# WorkerB.net
KiCad netlist of a schematic drawn in EAGLE
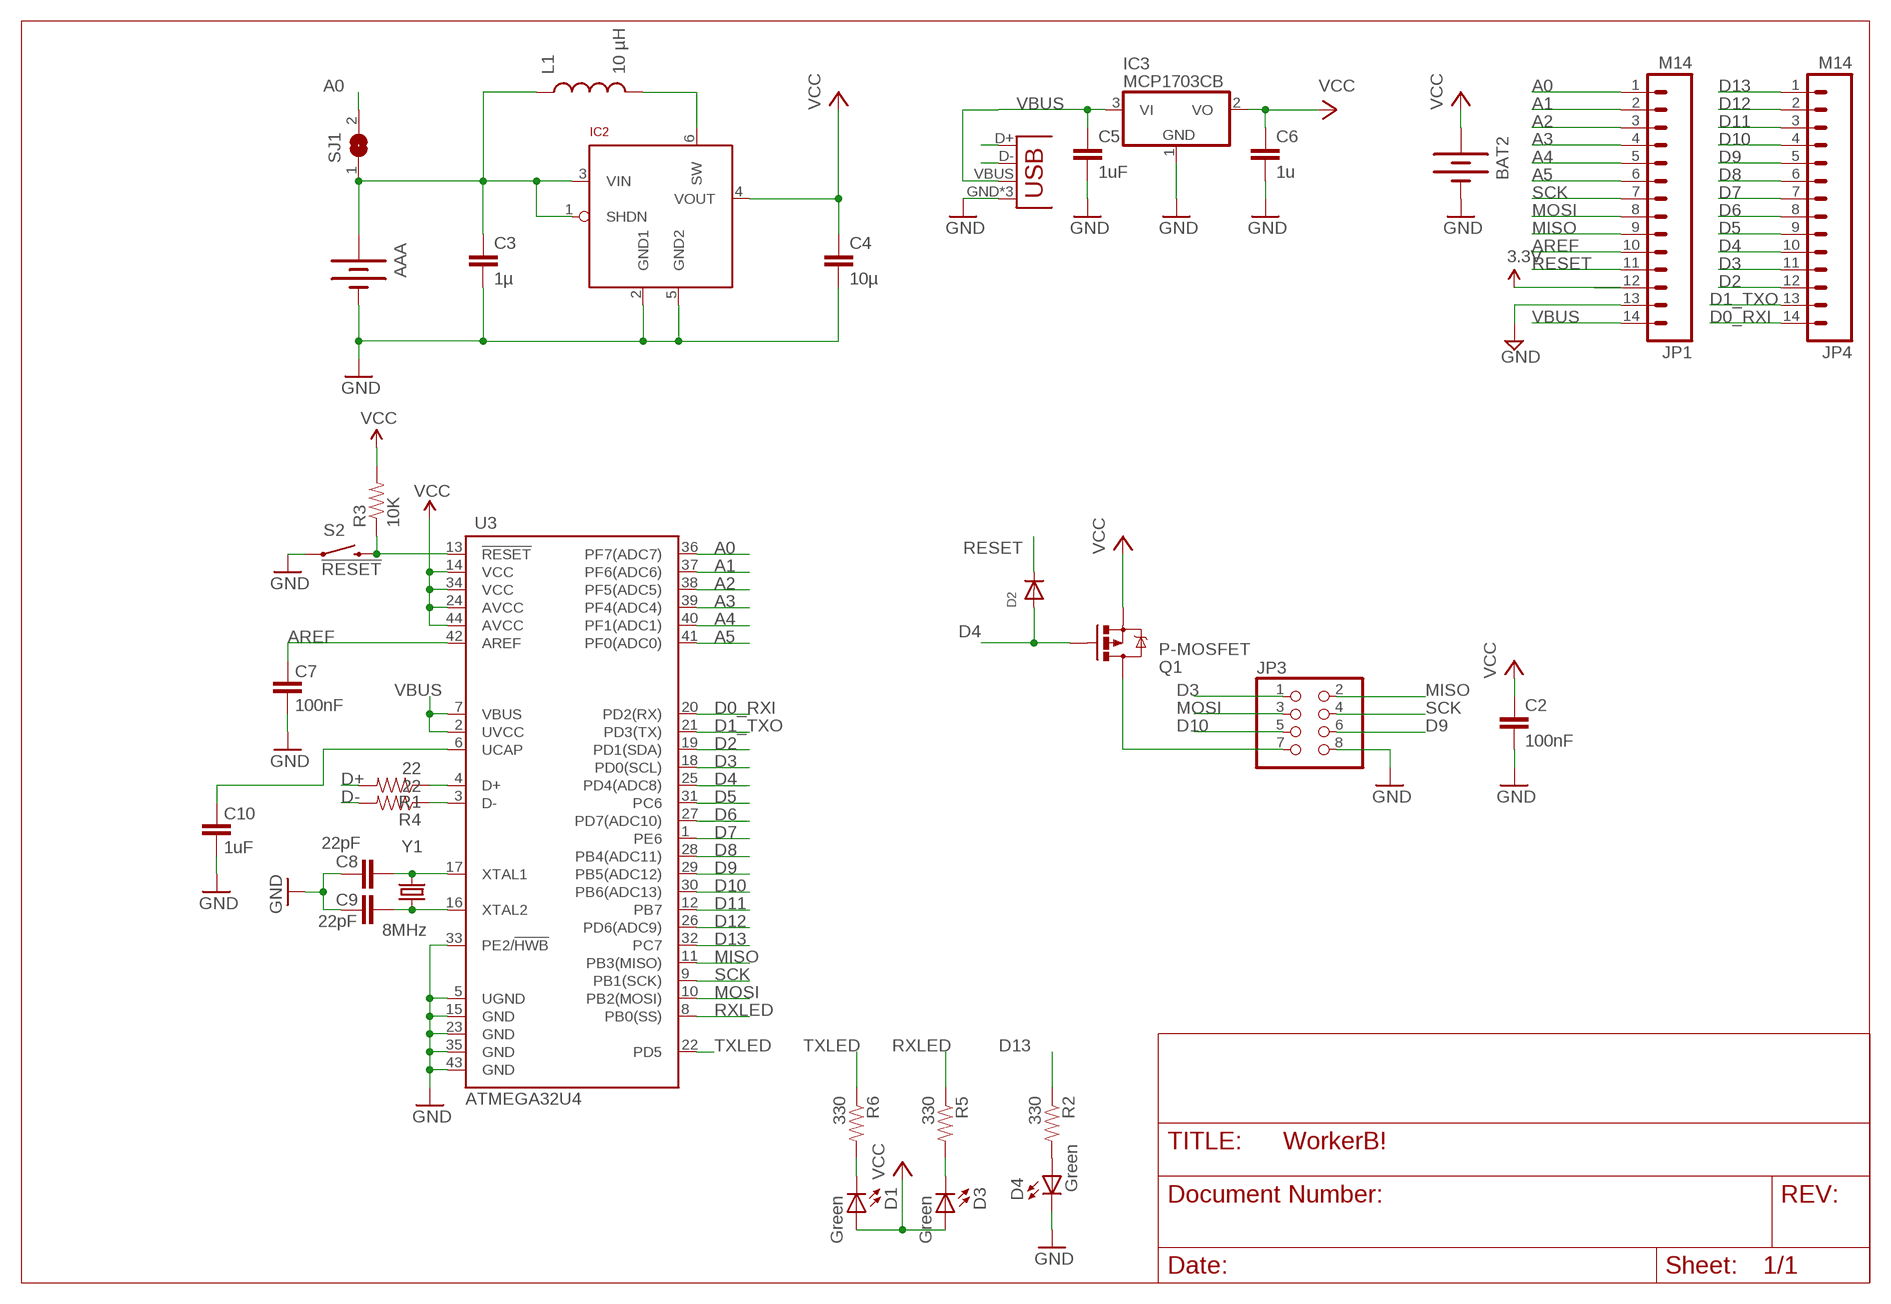
[diagram p0: schematic, sheet 1]

(export (version "E")
  (design (tool "Eeschema 10.0.6"))
  (components
    (comp (ref "AAA")
      (value "BATTERYAAA-JL")
      (footprint "eagle-import:BATTERY-AAA-JL")
      (libsource (lib "eagle-import") (part "BATTERYAAA-JL"))
    )
    (comp (ref "BAT2")
      (value "BATTERY20PTH")
      (footprint "eagle-import:BATTCOM_20MM_PTH")
      (libsource (lib "eagle-import") (part "SparkFun_BATTERY20PTH"))
    )
    (comp (ref "C2")
      (value "100nF")
      (footprint "eagle-import:C0603K")
      (libsource (lib "eagle-import") (part "C-EUC0603K"))
    )
    (comp (ref "C3")
      (value "1µ")
      (footprint "eagle-import:0603-CAP")
      (libsource (lib "eagle-import") (part "CAP0603-CAP"))
    )
    (comp (ref "C4")
      (value "10µ")
      (footprint "eagle-import:0805")
      (libsource (lib "eagle-import") (part "CAP0805"))
    )
    (comp (ref "C5")
      (value "1uF")
      (footprint "eagle-import:C0603K")
      (libsource (lib "eagle-import") (part "C-EUC0603K"))
    )
    (comp (ref "C6")
      (value "1u")
      (footprint "eagle-import:C0603K")
      (libsource (lib "eagle-import") (part "C-EUC0603K"))
    )
    (comp (ref "C7")
      (value "100nF")
      (footprint "eagle-import:0402-CAP")
      (libsource (lib "eagle-import") (part "CAP0402-CAP"))
    )
    (comp (ref "C8")
      (value "22pF")
      (footprint "eagle-import:0402-CAP")
      (libsource (lib "eagle-import") (part "CAP0402-CAP"))
    )
    (comp (ref "C9")
      (value "22pF")
      (footprint "eagle-import:0402-CAP")
      (libsource (lib "eagle-import") (part "CAP0402-CAP"))
    )
    (comp (ref "C10")
      (value "1uF")
      (footprint "eagle-import:0402-CAP")
      (libsource (lib "eagle-import") (part "CAP0402-CAP"))
    )
    (comp (ref "D1")
      (value "Green")
      (footprint "eagle-import:LED-0603")
      (libsource (lib "eagle-import") (part "LED0603"))
    )
    (comp (ref "D2")
      (value "DIODESOD-323F")
      (footprint "eagle-import:SOD-323F")
      (libsource (lib "eagle-import") (part "DIODESOD-323F"))
    )
    (comp (ref "D3")
      (value "Green")
      (footprint "eagle-import:LED-0603")
      (libsource (lib "eagle-import") (part "LED0603"))
    )
    (comp (ref "D4")
      (value "Green")
      (footprint "eagle-import:LED-0603")
      (libsource (lib "eagle-import") (part "LED0603"))
    )
    (comp (ref "IC2")
      (value "LTC3525")
      (footprint "eagle-import:SC70")
      (libsource (lib "eagle-import") (part "LTC3525"))
    )
    (comp (ref "IC3")
      (value "MCP1703CB")
      (footprint "eagle-import:SOT23")
      (libsource (lib "eagle-import") (part "MCP1703CB"))
    )
    (comp (ref "JP1")
      (value "M14")
      (footprint "eagle-import:1X14")
      (libsource (lib "eagle-import") (part "M14"))
    )
    (comp (ref "JP2")
      (value "USB-MICROB")
      (footprint "eagle-import:USB-MICROB")
      (libsource (lib "eagle-import") (part "USB-MICROB"))
    )
    (comp (ref "JP3")
      (value "PINHD-2X4")
      (footprint "eagle-import:2X04")
      (libsource (lib "eagle-import") (part "PINHD-2X4"))
    )
    (comp (ref "JP4")
      (value "M14")
      (footprint "eagle-import:1X14")
      (libsource (lib "eagle-import") (part "M14"))
    )
    (comp (ref "L1")
      (value "10 µH")
      (footprint "eagle-import:1210")
      (libsource (lib "eagle-import") (part "INDUCTOR1210"))
    )
    (comp (ref "Q1")
      (value "P-MOSFET")
      (footprint "eagle-import:SOT23")
      (libsource (lib "eagle-import") (part "MOSFET-PCHANNEL"))
    )
    (comp (ref "R1")
      (value "22")
      (footprint "eagle-import:0402-RES")
      (libsource (lib "eagle-import") (part "RESISTOR0402-RES"))
    )
    (comp (ref "R2")
      (value "330")
      (footprint "eagle-import:0402-RES")
      (libsource (lib "eagle-import") (part "RESISTOR0402-RES"))
    )
    (comp (ref "R3")
      (value "10K")
      (footprint "eagle-import:0402-RES")
      (libsource (lib "eagle-import") (part "RESISTOR0402-RES"))
    )
    (comp (ref "R4")
      (value "22")
      (footprint "eagle-import:0402-RES")
      (libsource (lib "eagle-import") (part "RESISTOR0402-RES"))
    )
    (comp (ref "R5")
      (value "330")
      (footprint "eagle-import:0402-RES")
      (libsource (lib "eagle-import") (part "RESISTOR0402-RES"))
    )
    (comp (ref "R6")
      (value "330")
      (footprint "eagle-import:0402-RES")
      (libsource (lib "eagle-import") (part "RESISTOR0402-RES"))
    )
    (comp (ref "S2")
      (value "!RESET")
      (footprint "eagle-import:TACTILE_SWITCH_SMD")
      (libsource (lib "eagle-import") (part "SWITCH-MOMENTARY-2SMD"))
    )
    (comp (ref "SJ1") (value "SJ") (footprint "eagle-import:SJ") (libsource (lib "eagle-import") (part "SJ")))
    (comp (ref "U3")
      (value "ATMEGA32U4")
      (footprint "eagle-import:QFN-44-NOPAD")
      (libsource (lib "eagle-import") (part "ATMEGA32U4QFN2"))
    )
    (comp (ref "Y1")
      (value "8MHz")
      (footprint "eagle-import:CRYSTAL-SMD-5X3")
      (libsource (lib "eagle-import") (part "CRYSTAL5X3"))
    )
  )
  (nets
    (net (code "1") (name "/A0") (class "Default")
      (node (ref "JP1") (pin "1") (pinfunction "1_1") (pintype "passive"))
      (node (ref "SJ1") (pin "2") (pinfunction "2_2") (pintype "passive"))
      (node (ref "U3") (pin "36") (pinfunction "PF7(ADC7)_36") (pintype "bidirectional"))
    )
    (net (code "2") (name "/A1") (class "Default")
      (node (ref "JP1") (pin "2") (pinfunction "2_2") (pintype "passive"))
      (node (ref "U3") (pin "37") (pinfunction "PF6(ADC6)_37") (pintype "bidirectional"))
    )
    (net (code "3") (name "/A2") (class "Default")
      (node (ref "JP1") (pin "3") (pinfunction "3_3") (pintype "passive"))
      (node (ref "U3") (pin "38") (pinfunction "PF5(ADC5)_38") (pintype "bidirectional"))
    )
    (net (code "4") (name "/A3") (class "Default")
      (node (ref "JP1") (pin "4") (pinfunction "4_4") (pintype "passive"))
      (node (ref "U3") (pin "39") (pinfunction "PF4(ADC4)_39") (pintype "bidirectional"))
    )
    (net (code "5") (name "/A4") (class "Default")
      (node (ref "JP1") (pin "5") (pinfunction "5_5") (pintype "passive"))
      (node (ref "U3") (pin "40") (pinfunction "PF1(ADC1)_40") (pintype "bidirectional"))
    )
    (net (code "6") (name "/A5") (class "Default")
      (node (ref "JP1") (pin "6") (pinfunction "6_6") (pintype "passive"))
      (node (ref "U3") (pin "41") (pinfunction "PF0(ADC0)_41") (pintype "bidirectional"))
    )
    (net (code "7") (name "/AREF") (class "Default")
      (node (ref "C7") (pin "2") (pinfunction "2_2") (pintype "passive"))
      (node (ref "JP1") (pin "10") (pinfunction "10_10") (pintype "passive"))
      (node (ref "U3") (pin "42") (pinfunction "AREF_42") (pintype "bidirectional"))
    )
    (net (code "8") (name "/D+") (class "Default")
      (node (ref "JP2") (pin "D+") (pinfunction "D+_D+") (pintype "bidirectional"))
      (node (ref "R1") (pin "2") (pinfunction "2_2") (pintype "passive"))
    )
    (net (code "9") (name "/D-") (class "Default")
      (node (ref "JP2") (pin "D-") (pinfunction "D-_D-") (pintype "bidirectional"))
      (node (ref "R4") (pin "2") (pinfunction "2_2") (pintype "passive"))
    )
    (net (code "10") (name "/D0_RXI") (class "Default")
      (node (ref "JP4") (pin "14") (pinfunction "14_14") (pintype "passive"))
      (node (ref "U3") (pin "20") (pinfunction "PD2(RX)_20") (pintype "bidirectional"))
    )
    (net (code "11") (name "/D1_TXO") (class "Default")
      (node (ref "JP4") (pin "13") (pinfunction "13_13") (pintype "passive"))
      (node (ref "U3") (pin "21") (pinfunction "PD3(TX)_21") (pintype "bidirectional"))
    )
    (net (code "12") (name "/D2") (class "Default")
      (node (ref "JP4") (pin "12") (pinfunction "12_12") (pintype "passive"))
      (node (ref "U3") (pin "19") (pinfunction "PD1(SDA)_19") (pintype "bidirectional"))
    )
    (net (code "13") (name "/D3") (class "Default")
      (node (ref "JP3") (pin "1") (pinfunction "1_1") (pintype "passive"))
      (node (ref "JP4") (pin "11") (pinfunction "11_11") (pintype "passive"))
      (node (ref "U3") (pin "18") (pinfunction "PD0(SCL)_18") (pintype "bidirectional"))
    )
    (net (code "14") (name "/D4") (class "Default")
      (node (ref "D2") (pin "A") (pinfunction "A_A") (pintype "passive"))
      (node (ref "JP4") (pin "10") (pinfunction "10_10") (pintype "passive"))
      (node (ref "Q1") (pin "1") (pinfunction "G_1") (pintype "passive"))
      (node (ref "U3") (pin "25") (pinfunction "PD4(ADC8)_25") (pintype "bidirectional"))
    )
    (net (code "15") (name "/D5") (class "Default")
      (node (ref "JP4") (pin "9") (pinfunction "9_9") (pintype "passive"))
      (node (ref "U3") (pin "31") (pinfunction "PC6_31") (pintype "bidirectional"))
    )
    (net (code "16") (name "/D6") (class "Default")
      (node (ref "JP4") (pin "8") (pinfunction "8_8") (pintype "passive"))
      (node (ref "U3") (pin "27") (pinfunction "PD7(ADC10)_27") (pintype "bidirectional"))
    )
    (net (code "17") (name "/D7") (class "Default")
      (node (ref "JP4") (pin "7") (pinfunction "7_7") (pintype "passive"))
      (node (ref "U3") (pin "1") (pinfunction "PE6_1") (pintype "bidirectional"))
    )
    (net (code "18") (name "/D8") (class "Default")
      (node (ref "JP4") (pin "6") (pinfunction "6_6") (pintype "passive"))
      (node (ref "U3") (pin "28") (pinfunction "PB4(ADC11)_28") (pintype "bidirectional"))
    )
    (net (code "19") (name "/D9") (class "Default")
      (node (ref "JP3") (pin "6") (pinfunction "6_6") (pintype "passive"))
      (node (ref "JP4") (pin "5") (pinfunction "5_5") (pintype "passive"))
      (node (ref "U3") (pin "29") (pinfunction "PB5(ADC12)_29") (pintype "bidirectional"))
    )
    (net (code "20") (name "/D10") (class "Default")
      (node (ref "JP3") (pin "5") (pinfunction "5_5") (pintype "passive"))
      (node (ref "JP4") (pin "4") (pinfunction "4_4") (pintype "passive"))
      (node (ref "U3") (pin "30") (pinfunction "PB6(ADC13)_30") (pintype "bidirectional"))
    )
    (net (code "21") (name "/D11") (class "Default")
      (node (ref "JP4") (pin "3") (pinfunction "3_3") (pintype "passive"))
      (node (ref "U3") (pin "12") (pinfunction "PB7_12") (pintype "bidirectional"))
    )
    (net (code "22") (name "/D12") (class "Default")
      (node (ref "JP4") (pin "2") (pinfunction "2_2") (pintype "passive"))
      (node (ref "U3") (pin "26") (pinfunction "PD6(ADC9)_26") (pintype "bidirectional"))
    )
    (net (code "23") (name "/D13") (class "Default")
      (node (ref "JP4") (pin "1") (pinfunction "1_1") (pintype "passive"))
      (node (ref "R2") (pin "1") (pinfunction "1_1") (pintype "passive"))
      (node (ref "U3") (pin "32") (pinfunction "PC7_32") (pintype "bidirectional"))
    )
    (net (code "24") (name "/MISO") (class "Default")
      (node (ref "JP1") (pin "9") (pinfunction "9_9") (pintype "passive"))
      (node (ref "JP3") (pin "2") (pinfunction "2_2") (pintype "passive"))
      (node (ref "U3") (pin "11") (pinfunction "PB3(MISO)_11") (pintype "bidirectional"))
    )
    (net (code "25") (name "/MOSI") (class "Default")
      (node (ref "JP1") (pin "8") (pinfunction "8_8") (pintype "passive"))
      (node (ref "JP3") (pin "3") (pinfunction "3_3") (pintype "passive"))
      (node (ref "U3") (pin "10") (pinfunction "PB2(MOSI)_10") (pintype "bidirectional"))
    )
    (net (code "26") (name "/RESET") (class "Default")
      (node (ref "D2") (pin "C") (pinfunction "C_C") (pintype "passive"))
      (node (ref "JP1") (pin "11") (pinfunction "11_11") (pintype "passive"))
      (node (ref "R3") (pin "1") (pinfunction "1_1") (pintype "passive"))
      (node (ref "S2") (pin "3") (pinfunction "2_3") (pintype "passive"))
      (node (ref "U3") (pin "13") (pinfunction "~{RESET}_13") (pintype "bidirectional"))
    )
    (net (code "27") (name "/RXLED") (class "Default")
      (node (ref "R5") (pin "1") (pinfunction "1_1") (pintype "passive"))
      (node (ref "U3") (pin "8") (pinfunction "PB0(SS)_8") (pintype "bidirectional"))
    )
    (net (code "28") (name "/SCK") (class "Default")
      (node (ref "JP1") (pin "7") (pinfunction "7_7") (pintype "passive"))
      (node (ref "JP3") (pin "4") (pinfunction "4_4") (pintype "passive"))
      (node (ref "U3") (pin "9") (pinfunction "PB1(SCK)_9") (pintype "bidirectional"))
    )
    (net (code "29") (name "/TXLED") (class "Default")
      (node (ref "R6") (pin "1") (pinfunction "1_1") (pintype "passive"))
      (node (ref "U3") (pin "22") (pinfunction "PD5_22") (pintype "bidirectional"))
    )
    (net (code "30") (name "/VBUS") (class "Default")
      (node (ref "C5") (pin "1") (pinfunction "1_1") (pintype "passive"))
      (node (ref "IC3") (pin "3") (pinfunction "VI_3") (pintype "input"))
      (node (ref "JP1") (pin "14") (pinfunction "14_14") (pintype "passive"))
      (node (ref "JP2") (pin "VBUS") (pinfunction "VBUS_VBUS") (pintype "bidirectional"))
      (node (ref "U3") (pin "2") (pinfunction "UVCC_2") (pintype "bidirectional"))
      (node (ref "U3") (pin "7") (pinfunction "VBUS_7") (pintype "bidirectional"))
    )
    (net (code "31") (name "3.3V") (class "Default")
      (node (ref "BAT2") (pin "1") (pinfunction "+_1") (pintype "power_in"))
      (node (ref "C2") (pin "1") (pinfunction "1_1") (pintype "passive"))
      (node (ref "C4") (pin "1") (pinfunction "1_1") (pintype "passive"))
      (node (ref "C6") (pin "1") (pinfunction "1_1") (pintype "passive"))
      (node (ref "D1") (pin "A") (pinfunction "A_A") (pintype "passive"))
      (node (ref "D3") (pin "A") (pinfunction "A_A") (pintype "passive"))
      (node (ref "IC2") (pin "4") (pinfunction "VOUT_4") (pintype "power_in"))
      (node (ref "IC3") (pin "2") (pinfunction "VO_2") (pintype "passive"))
      (node (ref "JP1") (pin "12") (pinfunction "12_12") (pintype "passive"))
      (node (ref "Q1") (pin "2") (pinfunction "S_2") (pintype "passive"))
      (node (ref "R3") (pin "2") (pinfunction "2_2") (pintype "passive"))
      (node (ref "U3") (pin "14") (pinfunction "VCC_14") (pintype "bidirectional"))
      (node (ref "U3") (pin "24") (pinfunction "AVCC_24") (pintype "bidirectional"))
      (node (ref "U3") (pin "34") (pinfunction "VCC_34") (pintype "bidirectional"))
      (node (ref "U3") (pin "44") (pinfunction "AVCC_44") (pintype "bidirectional"))
    )
    (net (code "32") (name "GND") (class "Default")
      (node (ref "AAA") (pin "GND@1") (pinfunction "-_GND@1") (pintype "power_in"))
      (node (ref "BAT2") (pin "2") (pinfunction "-_2") (pintype "power_in"))
      (node (ref "C10") (pin "1") (pinfunction "1_1") (pintype "passive"))
      (node (ref "C2") (pin "2") (pinfunction "2_2") (pintype "passive"))
      (node (ref "C3") (pin "2") (pinfunction "2_2") (pintype "passive"))
      (node (ref "C4") (pin "2") (pinfunction "2_2") (pintype "passive"))
      (node (ref "C5") (pin "2") (pinfunction "2_2") (pintype "passive"))
      (node (ref "C6") (pin "2") (pinfunction "2_2") (pintype "passive"))
      (node (ref "C7") (pin "1") (pinfunction "1_1") (pintype "passive"))
      (node (ref "C8") (pin "2") (pinfunction "2_2") (pintype "passive"))
      (node (ref "C9") (pin "2") (pinfunction "2_2") (pintype "passive"))
      (node (ref "D4") (pin "C") (pinfunction "C_C") (pintype "passive"))
      (node (ref "IC2") (pin "2") (pinfunction "GND1_2") (pintype "power_in"))
      (node (ref "IC2") (pin "5") (pinfunction "GND2_5") (pintype "power_in"))
      (node (ref "IC3") (pin "1") (pinfunction "GND_1") (pintype "passive"))
      (node (ref "JP1") (pin "13") (pinfunction "13_13") (pintype "passive"))
      (node (ref "JP2") (pin "GND") (pinfunction "GND_GND") (pintype "bidirectional"))
      (node (ref "JP2") (pin "MT1") (pinfunction "GND_MT1") (pintype "bidirectional"))
      (node (ref "JP2") (pin "MT2") (pinfunction "GND_MT2") (pintype "bidirectional"))
      (node (ref "JP3") (pin "8") (pinfunction "8_8") (pintype "passive"))
      (node (ref "S2") (pin "1") (pinfunction "1_1") (pintype "passive"))
      (node (ref "U3") (pin "15") (pinfunction "GND_15") (pintype "bidirectional"))
      (node (ref "U3") (pin "23") (pinfunction "GND_23") (pintype "bidirectional"))
      (node (ref "U3") (pin "33") (pinfunction "PE2/~{HWB}_33") (pintype "bidirectional"))
      (node (ref "U3") (pin "35") (pinfunction "GND_35") (pintype "bidirectional"))
      (node (ref "U3") (pin "43") (pinfunction "GND_43") (pintype "bidirectional"))
      (node (ref "U3") (pin "5") (pinfunction "UGND_5") (pintype "bidirectional"))
    )
    (net (code "33") (name "Net-(AAA-+)") (class "Default")
      (node (ref "AAA") (pin "PWR@1") (pinfunction "+_PWR@1") (pintype "power_in"))
      (node (ref "C3") (pin "1") (pinfunction "1_1") (pintype "passive"))
      (node (ref "IC2") (pin "1") (pinfunction "SHDN_1") (pintype "input"))
      (node (ref "IC2") (pin "3") (pinfunction "VIN_3") (pintype "tri_state"))
      (node (ref "L1") (pin "1") (pinfunction "1_1") (pintype "passive"))
      (node (ref "SJ1") (pin "1") (pinfunction "1_1") (pintype "passive"))
    )
    (net (code "34") (name "Net-(D1-PadC)") (class "Default")
      (node (ref "D1") (pin "C") (pinfunction "C_C") (pintype "passive"))
      (node (ref "R6") (pin "2") (pinfunction "2_2") (pintype "passive"))
    )
    (net (code "35") (name "Net-(D3-PadC)") (class "Default")
      (node (ref "D3") (pin "C") (pinfunction "C_C") (pintype "passive"))
      (node (ref "R5") (pin "2") (pinfunction "2_2") (pintype "passive"))
    )
    (net (code "36") (name "Net-(D4-PadA)") (class "Default")
      (node (ref "D4") (pin "A") (pinfunction "A_A") (pintype "passive"))
      (node (ref "R2") (pin "2") (pinfunction "2_2") (pintype "passive"))
    )
    (net (code "37") (name "Net-(IC2-SW)") (class "Default")
      (node (ref "IC2") (pin "6") (pinfunction "SW_6") (pintype "power_in"))
      (node (ref "L1") (pin "2") (pinfunction "2_2") (pintype "passive"))
    )
    (net (code "38") (name "Net-(Q1-D)") (class "Default")
      (node (ref "JP3") (pin "7") (pinfunction "7_7") (pintype "passive"))
      (node (ref "Q1") (pin "3") (pinfunction "D_3") (pintype "passive"))
    )
    (net (code "39") (name "Net-(U3-D+)") (class "Default")
      (node (ref "R1") (pin "1") (pinfunction "1_1") (pintype "passive"))
      (node (ref "U3") (pin "4") (pinfunction "D+_4") (pintype "bidirectional"))
    )
    (net (code "40") (name "Net-(U3-D-)") (class "Default")
      (node (ref "R4") (pin "1") (pinfunction "1_1") (pintype "passive"))
      (node (ref "U3") (pin "3") (pinfunction "D-_3") (pintype "bidirectional"))
    )
    (net (code "41") (name "Net-(U3-UCAP)") (class "Default")
      (node (ref "C10") (pin "2") (pinfunction "2_2") (pintype "passive"))
      (node (ref "U3") (pin "6") (pinfunction "UCAP_6") (pintype "bidirectional"))
    )
    (net (code "42") (name "Net-(U3-XTAL1)") (class "Default")
      (node (ref "C8") (pin "1") (pinfunction "1_1") (pintype "passive"))
      (node (ref "U3") (pin "17") (pinfunction "XTAL1_17") (pintype "bidirectional"))
      (node (ref "Y1") (pin "3") (pinfunction "2_3") (pintype "passive"))
    )
    (net (code "43") (name "Net-(U3-XTAL2)") (class "Default")
      (node (ref "C9") (pin "1") (pinfunction "1_1") (pintype "passive"))
      (node (ref "U3") (pin "16") (pinfunction "XTAL2_16") (pintype "bidirectional"))
      (node (ref "Y1") (pin "1") (pinfunction "1_1") (pintype "passive"))
    )
  )
)
